# ATtiny10Shield.net
KiCad netlist of a schematic drawn in EAGLE
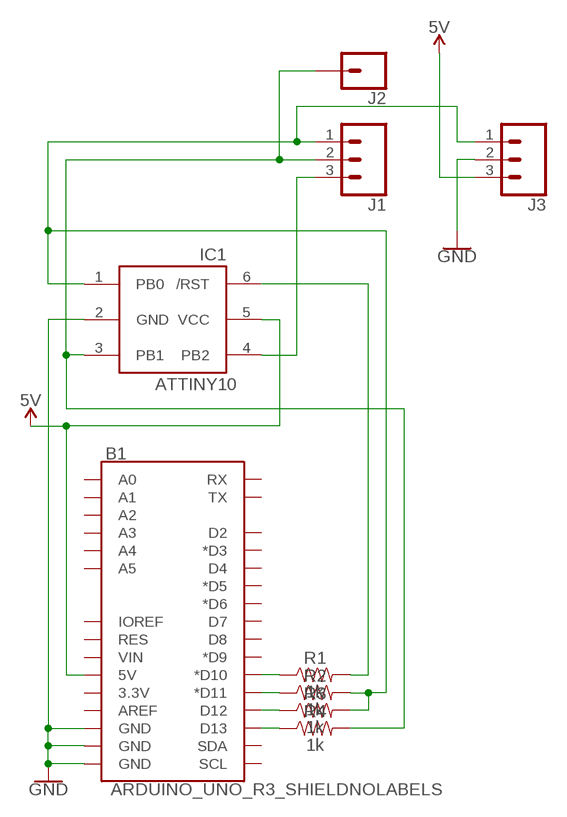
[diagram p0: schematic, sheet 1]

(export (version "E")
  (design (tool "Eeschema 10.0.6"))
  (components
    (comp (ref "B1")
      (value "ARDUINO_UNO_R3_SHIELDNOLABELS")
      (footprint "eagle-import:UNO_R3_SHIELD_NOLABELS")
      (libsource (lib "eagle-import") (part "ARDUINO_UNO_R3_SHIELDNOLABELS"))
    )
    (comp (ref "IC1")
      (value "ATTINY10")
      (footprint "eagle-import:SOT23-6")
      (libsource (lib "eagle-import") (part "ATTINY10"))
    )
    (comp (ref "J1")
      (value "CONN_03")
      (footprint "eagle-import:1X03")
      (libsource (lib "eagle-import") (part "CONN_03"))
    )
    (comp (ref "J2")
      (value "CONN_01")
      (footprint "eagle-import:1X01")
      (libsource (lib "eagle-import") (part "CONN_01"))
    )
    (comp (ref "J3")
      (value "CONN_03")
      (footprint "eagle-import:1X03")
      (libsource (lib "eagle-import") (part "CONN_03"))
    )
    (comp (ref "R1")
      (value "1k")
      (footprint "eagle-import:AXIAL-0.3")
      (libsource (lib "eagle-import") (part "1KOHM-HORIZ-1/4W-1%"))
    )
    (comp (ref "R2")
      (value "1k")
      (footprint "eagle-import:AXIAL-0.3")
      (libsource (lib "eagle-import") (part "1KOHM-HORIZ-1/4W-1%"))
    )
    (comp (ref "R3")
      (value "1k")
      (footprint "eagle-import:AXIAL-0.3")
      (libsource (lib "eagle-import") (part "1KOHM-HORIZ-1/4W-1%"))
    )
    (comp (ref "R4")
      (value "1k")
      (footprint "eagle-import:AXIAL-0.3")
      (libsource (lib "eagle-import") (part "1KOHM-HORIZ-1/4W-1%"))
    )
  )
  (nets
    (net (code "1") (name "5V") (class "Default")
      (node (ref "B1") (pin "5V") (pinfunction "5V_5V") (pintype "bidirectional"))
      (node (ref "IC1") (pin "5") (pinfunction "VCC_5") (pintype "power_in"))
      (node (ref "J3") (pin "3") (pinfunction "3_3") (pintype "passive"))
    )
    (net (code "2") (name "GND") (class "Default")
      (node (ref "B1") (pin "GND@0") (pinfunction "GND_GND@0") (pintype "bidirectional"))
      (node (ref "B1") (pin "GND@1") (pinfunction "GND_GND@1") (pintype "bidirectional"))
      (node (ref "B1") (pin "GND@2") (pinfunction "GND_GND@2") (pintype "bidirectional"))
      (node (ref "IC1") (pin "2") (pinfunction "GND_2") (pintype "power_in"))
      (node (ref "J3") (pin "2") (pinfunction "2_2") (pintype "passive"))
    )
    (net (code "3") (name "Net-(B1-*D10)") (class "Default")
      (node (ref "B1") (pin "D10") (pinfunction "*D10_D10") (pintype "bidirectional"))
      (node (ref "R1") (pin "P$1") (pinfunction "1_P$1") (pintype "passive"))
    )
    (net (code "4") (name "Net-(B1-*D11)") (class "Default")
      (node (ref "B1") (pin "D11") (pinfunction "*D11_D11") (pintype "bidirectional"))
      (node (ref "R2") (pin "P$1") (pinfunction "1_P$1") (pintype "passive"))
    )
    (net (code "5") (name "Net-(IC1-PB0)") (class "Default")
      (node (ref "IC1") (pin "1") (pinfunction "PB0_1") (pintype "bidirectional"))
      (node (ref "J1") (pin "1") (pinfunction "1_1") (pintype "passive"))
      (node (ref "J3") (pin "1") (pinfunction "1_1") (pintype "passive"))
      (node (ref "R2") (pin "P$2") (pinfunction "2_P$2") (pintype "passive"))
      (node (ref "R3") (pin "P$2") (pinfunction "2_P$2") (pintype "passive"))
    )
    (net (code "6") (name "Net-(IC1-PB1)") (class "Default")
      (node (ref "IC1") (pin "3") (pinfunction "PB1_3") (pintype "bidirectional"))
      (node (ref "J1") (pin "2") (pinfunction "2_2") (pintype "passive"))
      (node (ref "J2") (pin "1") (pinfunction "1_1") (pintype "passive"))
      (node (ref "R4") (pin "P$2") (pinfunction "2_P$2") (pintype "passive"))
    )
    (net (code "7") (name "Net-(IC1-PB2)") (class "Default")
      (node (ref "IC1") (pin "4") (pinfunction "PB2_4") (pintype "bidirectional"))
      (node (ref "J1") (pin "3") (pinfunction "3_3") (pintype "passive"))
    )
    (net (code "8") (name "Net-(IC1-{slash}RST)") (class "Default")
      (node (ref "IC1") (pin "6") (pinfunction "/RST_6") (pintype "bidirectional"))
      (node (ref "R1") (pin "P$2") (pinfunction "2_P$2") (pintype "passive"))
    )
    (net (code "9") (name "Net-(R3-1)") (class "Default")
      (node (ref "B1") (pin "D12") (pinfunction "D12_D12") (pintype "bidirectional"))
      (node (ref "R3") (pin "P$1") (pinfunction "1_P$1") (pintype "passive"))
    )
    (net (code "10") (name "Net-(R4-1)") (class "Default")
      (node (ref "B1") (pin "D13") (pinfunction "D13_D13") (pintype "bidirectional"))
      (node (ref "R4") (pin "P$1") (pinfunction "1_P$1") (pintype "passive"))
    )
    (net (code "11") (name "unconnected-(B1-*D3-PadD3)") (class "Default")
      (node (ref "B1") (pin "D3") (pinfunction "*D3_D3") (pintype "bidirectional"))
    )
    (net (code "12") (name "unconnected-(B1-*D5-PadD5)") (class "Default")
      (node (ref "B1") (pin "D5") (pinfunction "*D5_D5") (pintype "bidirectional"))
    )
    (net (code "13") (name "unconnected-(B1-*D6-PadD6)") (class "Default")
      (node (ref "B1") (pin "D6") (pinfunction "*D6_D6") (pintype "bidirectional"))
    )
    (net (code "14") (name "unconnected-(B1-*D9-PadD9)") (class "Default")
      (node (ref "B1") (pin "D9") (pinfunction "*D9_D9") (pintype "bidirectional"))
    )
    (net (code "15") (name "unconnected-(B1-Pad3.3V)") (class "Default")
      (node (ref "B1") (pin "3.3V") (pinfunction "3.3V_3.3V") (pintype "bidirectional"))
    )
    (net (code "16") (name "unconnected-(B1-PadA0)") (class "Default")
      (node (ref "B1") (pin "A0") (pinfunction "A0_A0") (pintype "bidirectional"))
    )
    (net (code "17") (name "unconnected-(B1-PadA1)") (class "Default")
      (node (ref "B1") (pin "A1") (pinfunction "A1_A1") (pintype "bidirectional"))
    )
    (net (code "18") (name "unconnected-(B1-PadA2)") (class "Default")
      (node (ref "B1") (pin "A2") (pinfunction "A2_A2") (pintype "bidirectional"))
    )
    (net (code "19") (name "unconnected-(B1-PadA3)") (class "Default")
      (node (ref "B1") (pin "A3") (pinfunction "A3_A3") (pintype "bidirectional"))
    )
    (net (code "20") (name "unconnected-(B1-PadA4)") (class "Default")
      (node (ref "B1") (pin "A4") (pinfunction "A4_A4") (pintype "bidirectional"))
    )
    (net (code "21") (name "unconnected-(B1-PadA5)") (class "Default")
      (node (ref "B1") (pin "A5") (pinfunction "A5_A5") (pintype "bidirectional"))
    )
    (net (code "22") (name "unconnected-(B1-PadAREF)") (class "Default")
      (node (ref "B1") (pin "AREF") (pinfunction "AREF_AREF") (pintype "bidirectional"))
    )
    (net (code "23") (name "unconnected-(B1-PadD2)") (class "Default")
      (node (ref "B1") (pin "D2") (pinfunction "D2_D2") (pintype "bidirectional"))
    )
    (net (code "24") (name "unconnected-(B1-PadD4)") (class "Default")
      (node (ref "B1") (pin "D4") (pinfunction "D4_D4") (pintype "bidirectional"))
    )
    (net (code "25") (name "unconnected-(B1-PadD7)") (class "Default")
      (node (ref "B1") (pin "D7") (pinfunction "D7_D7") (pintype "bidirectional"))
    )
    (net (code "26") (name "unconnected-(B1-PadD8)") (class "Default")
      (node (ref "B1") (pin "D8") (pinfunction "D8_D8") (pintype "bidirectional"))
    )
    (net (code "27") (name "unconnected-(B1-PadIOREF)") (class "Default")
      (node (ref "B1") (pin "IOREF") (pinfunction "IOREF_IOREF") (pintype "bidirectional"))
    )
    (net (code "28") (name "unconnected-(B1-PadRES)") (class "Default")
      (node (ref "B1") (pin "RES") (pinfunction "RES_RES") (pintype "bidirectional"))
    )
    (net (code "29") (name "unconnected-(B1-PadRX)") (class "Default")
      (node (ref "B1") (pin "RX") (pinfunction "RX_RX") (pintype "bidirectional"))
    )
    (net (code "30") (name "unconnected-(B1-PadSCL)") (class "Default")
      (node (ref "B1") (pin "SCL") (pinfunction "SCL_SCL") (pintype "bidirectional"))
    )
    (net (code "31") (name "unconnected-(B1-PadSDA)") (class "Default")
      (node (ref "B1") (pin "SDA") (pinfunction "SDA_SDA") (pintype "bidirectional"))
    )
    (net (code "32") (name "unconnected-(B1-PadTX)") (class "Default")
      (node (ref "B1") (pin "TX") (pinfunction "TX_TX") (pintype "bidirectional"))
    )
    (net (code "33") (name "unconnected-(B1-PadVIN)") (class "Default")
      (node (ref "B1") (pin "VIN") (pinfunction "VIN_VIN") (pintype "bidirectional"))
    )
  )
)
